# UI.net
KiCad netlist of a schematic drawn in Altium Designer
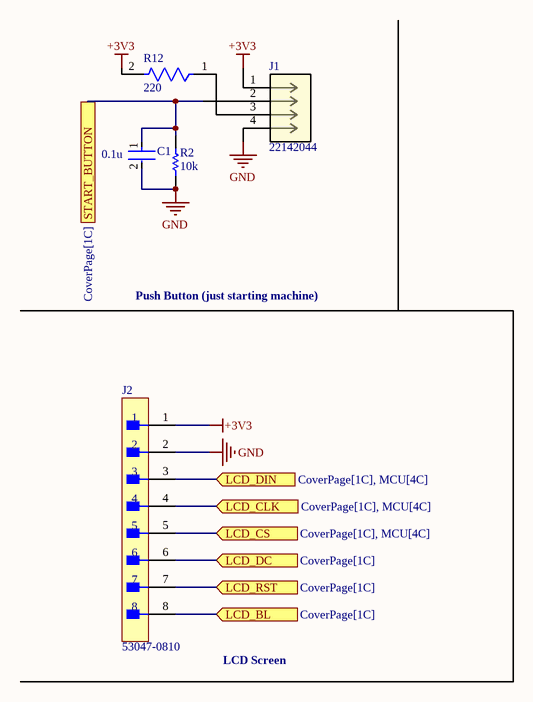
[diagram p0: UI.SchDoc]

(export (version "E")
  (design (tool "Eeschema 10.0.6"))
  (components
    (comp (ref "C1")
      (value "0.1u")
      (footprint "FP-CL21-IPC_A")
      (description "CL21 Series 0805 100nF 100V ±10% Tolerance X7R Multilayer Ceramic Chip Capacitor")
      (libsource (lib "Altium Content Vault") (part "b4654b650e69147ec39a6b967a45e02"))
    )
    (comp (ref "J1")
      (value "22142044")
      (footprint "CONN_SDA-4455_04_BE_MOL")
      (description "No Description Available")
      (libsource (lib "Northeastern University - Generate") (part "22142044"))
    )
    (comp (ref "J2")
      (value "53047-0810")
      (footprint "53047-0810_MFG")
      (description "Conn Shrouded Header (4 Sides) HDR 8 POS 1.25mm Solder ST Top Entry Thru-Hole PicoBlade Tray")
      (libsource (lib "Altium Content Vault") (part "46342ca634edb1a761f196181bcfdd6"))
    )
    (comp (ref "R2")
      (value "10k")
      (footprint "RESC2013X60X40LL20T25_A")
      (fields (field (name "TOLERANCE") "0.1%") (field (name "MANUFACTURER") "Panasonic"))
      (libsource (lib "Altium Content Vault") (part "RES-2"))
    )
    (comp (ref "R12")
      (value "220")
      (footprint "FP-CRCW0805-e3-MFG")
      (description "RES Thick Film, 330Ω, 1%, 0.125W, 100ppm/°C, 0805")
      (fields (field (name "TOLERANCE") "1%"))
      (libsource (lib "Altium Content Vault") (part "1029c3af85768c4190bb7ad29bc67b5"))
    )
  )
  (nets
    (net (code "1") (name "+3V3") (class "Default")
      (node (ref "J1") (pin "1") (pinfunction "1_1") (pintype "passive"))
      (node (ref "J2") (pin "1") (pinfunction "1_1") (pintype "passive"))
      (node (ref "R12") (pin "2") (pinfunction "2_2") (pintype "passive"))
    )
    (net (code "2") (name "/LCD_BL") (class "Default")
      (node (ref "J2") (pin "8") (pinfunction "8_8") (pintype "passive"))
    )
    (net (code "3") (name "/LCD_CLK") (class "Default")
      (node (ref "J2") (pin "4") (pinfunction "4_4") (pintype "passive"))
    )
    (net (code "4") (name "/LCD_CS") (class "Default")
      (node (ref "J2") (pin "5") (pinfunction "5_5") (pintype "passive"))
    )
    (net (code "5") (name "/LCD_DC") (class "Default")
      (node (ref "J2") (pin "6") (pinfunction "6_6") (pintype "passive"))
    )
    (net (code "6") (name "/LCD_DIN") (class "Default")
      (node (ref "J2") (pin "3") (pinfunction "3_3") (pintype "passive"))
    )
    (net (code "7") (name "/LCD_RST") (class "Default")
      (node (ref "J2") (pin "7") (pinfunction "7_7") (pintype "passive"))
    )
    (net (code "8") (name "/START_BUTTON") (class "Default")
      (node (ref "C1") (pin "1") (pinfunction "1_1") (pintype "passive"))
      (node (ref "J1") (pin "2") (pinfunction "2_2") (pintype "passive"))
      (node (ref "R2") (pin "2") (pinfunction "2_2") (pintype "passive"))
    )
    (net (code "9") (name "GND") (class "Default")
      (node (ref "C1") (pin "2") (pinfunction "2_2") (pintype "passive"))
      (node (ref "J1") (pin "4") (pinfunction "4_4") (pintype "passive"))
      (node (ref "J2") (pin "2") (pinfunction "2_2") (pintype "passive"))
      (node (ref "R2") (pin "1") (pinfunction "1_1") (pintype "passive"))
    )
    (net (code "10") (name "Net-(J1-Pad3)") (class "Default")
      (node (ref "J1") (pin "3") (pinfunction "3_3") (pintype "passive"))
      (node (ref "R12") (pin "1") (pinfunction "1_1") (pintype "passive"))
    )
  )
)
